# Vectr.net
KiCad netlist of a schematic drawn in EAGLE
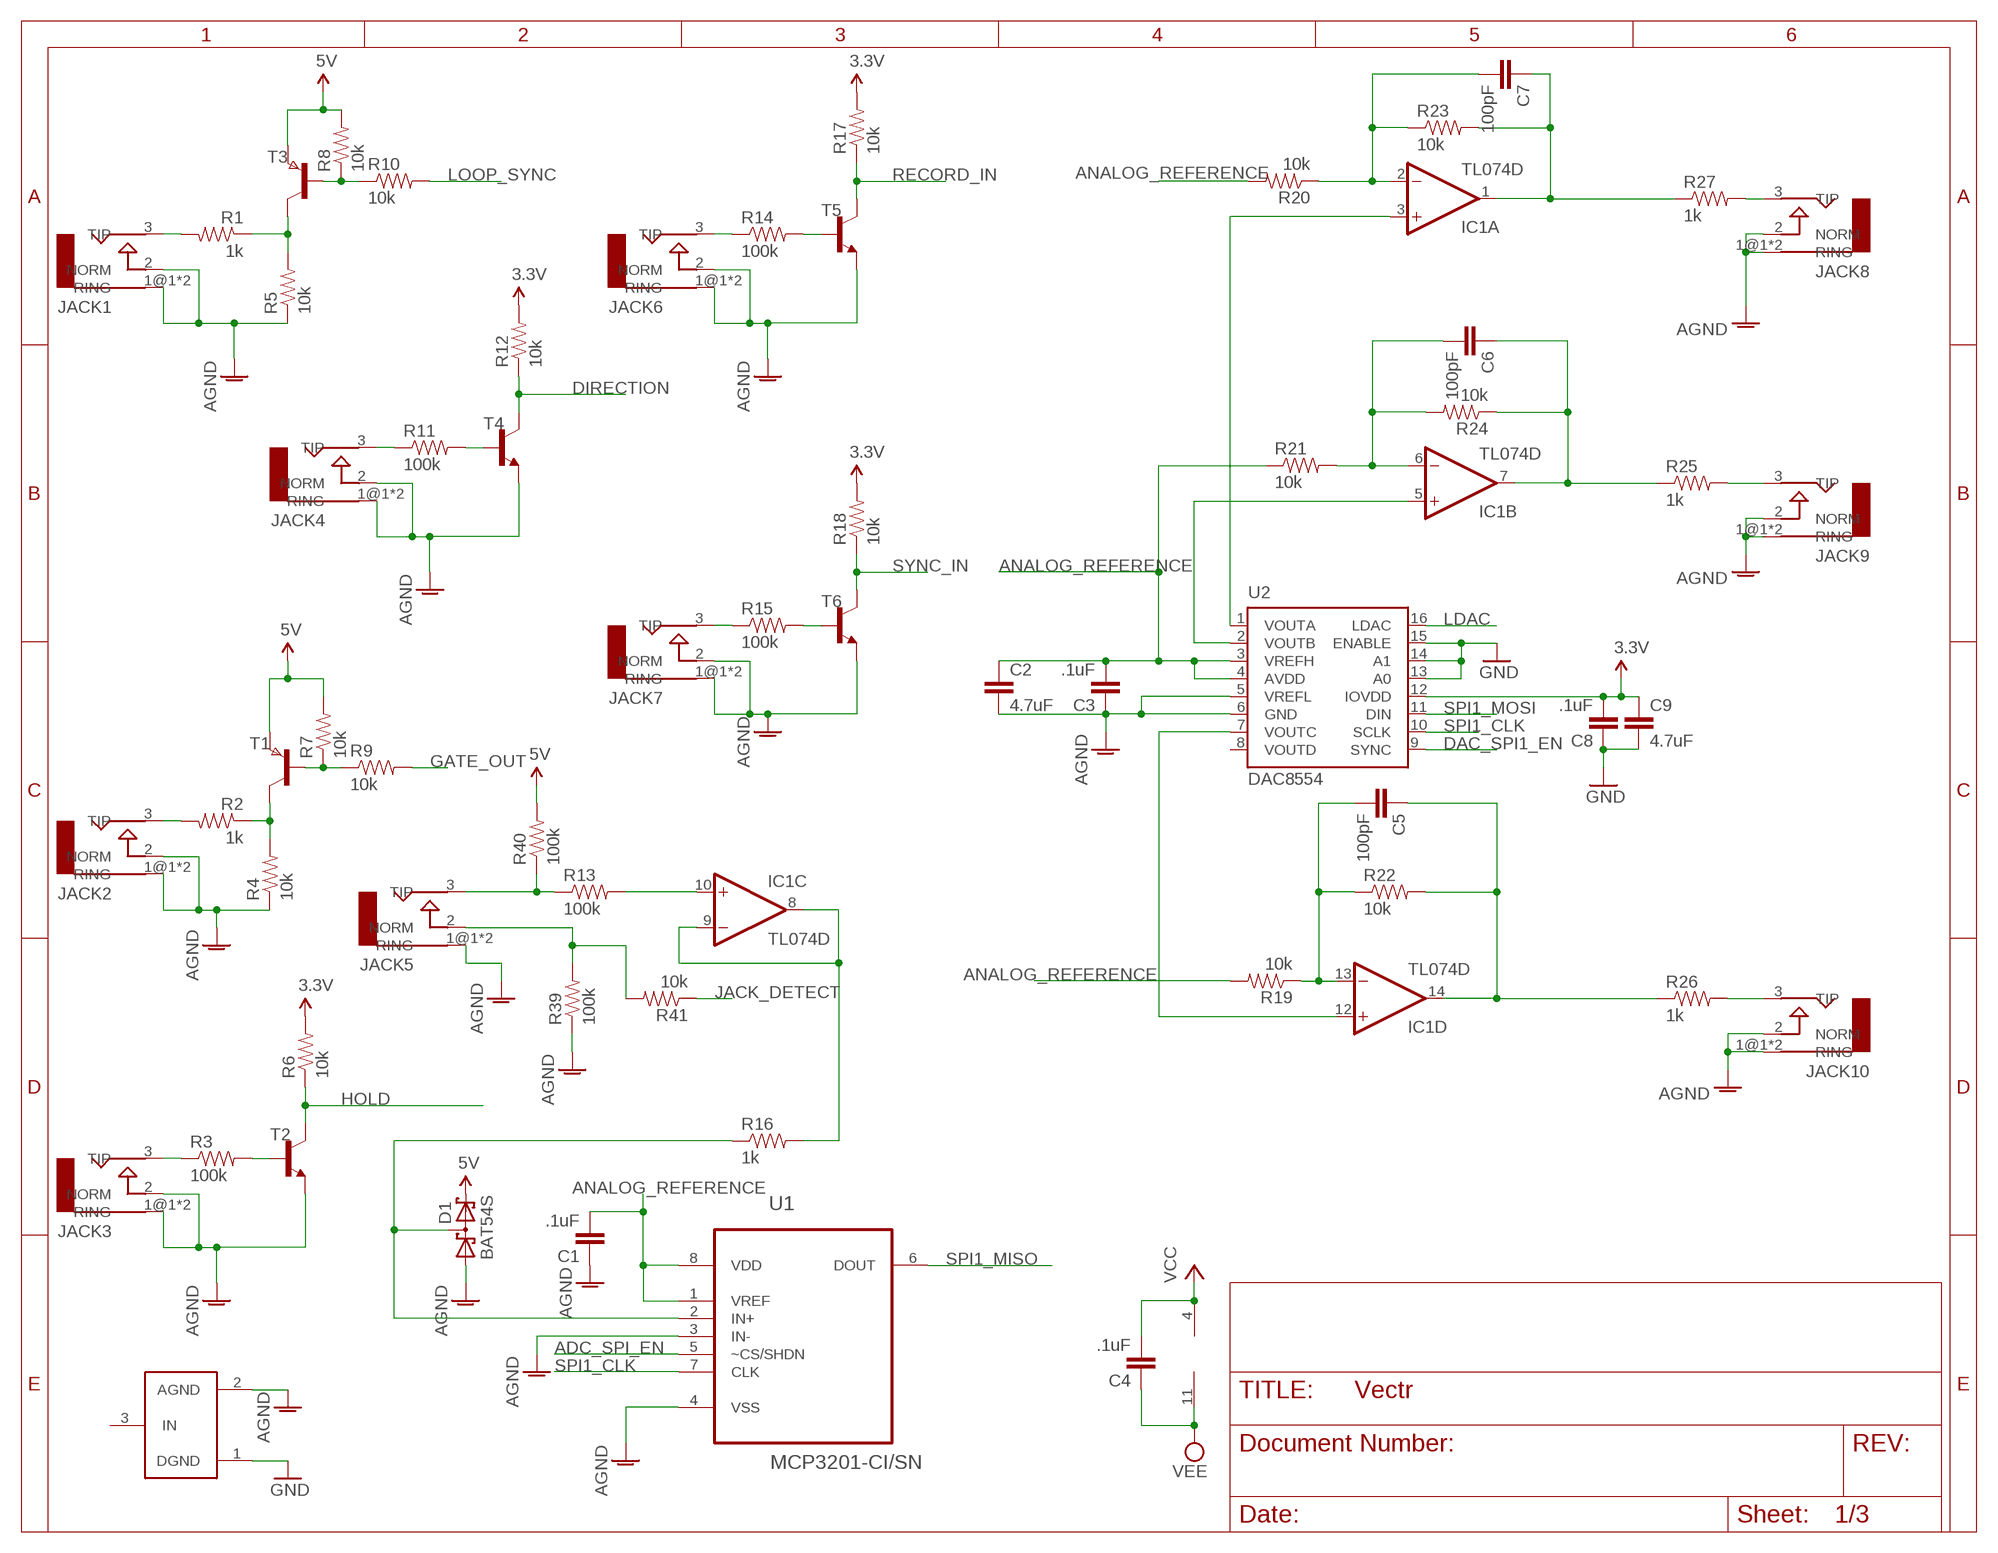
[diagram p0: schematic, sheet 1]
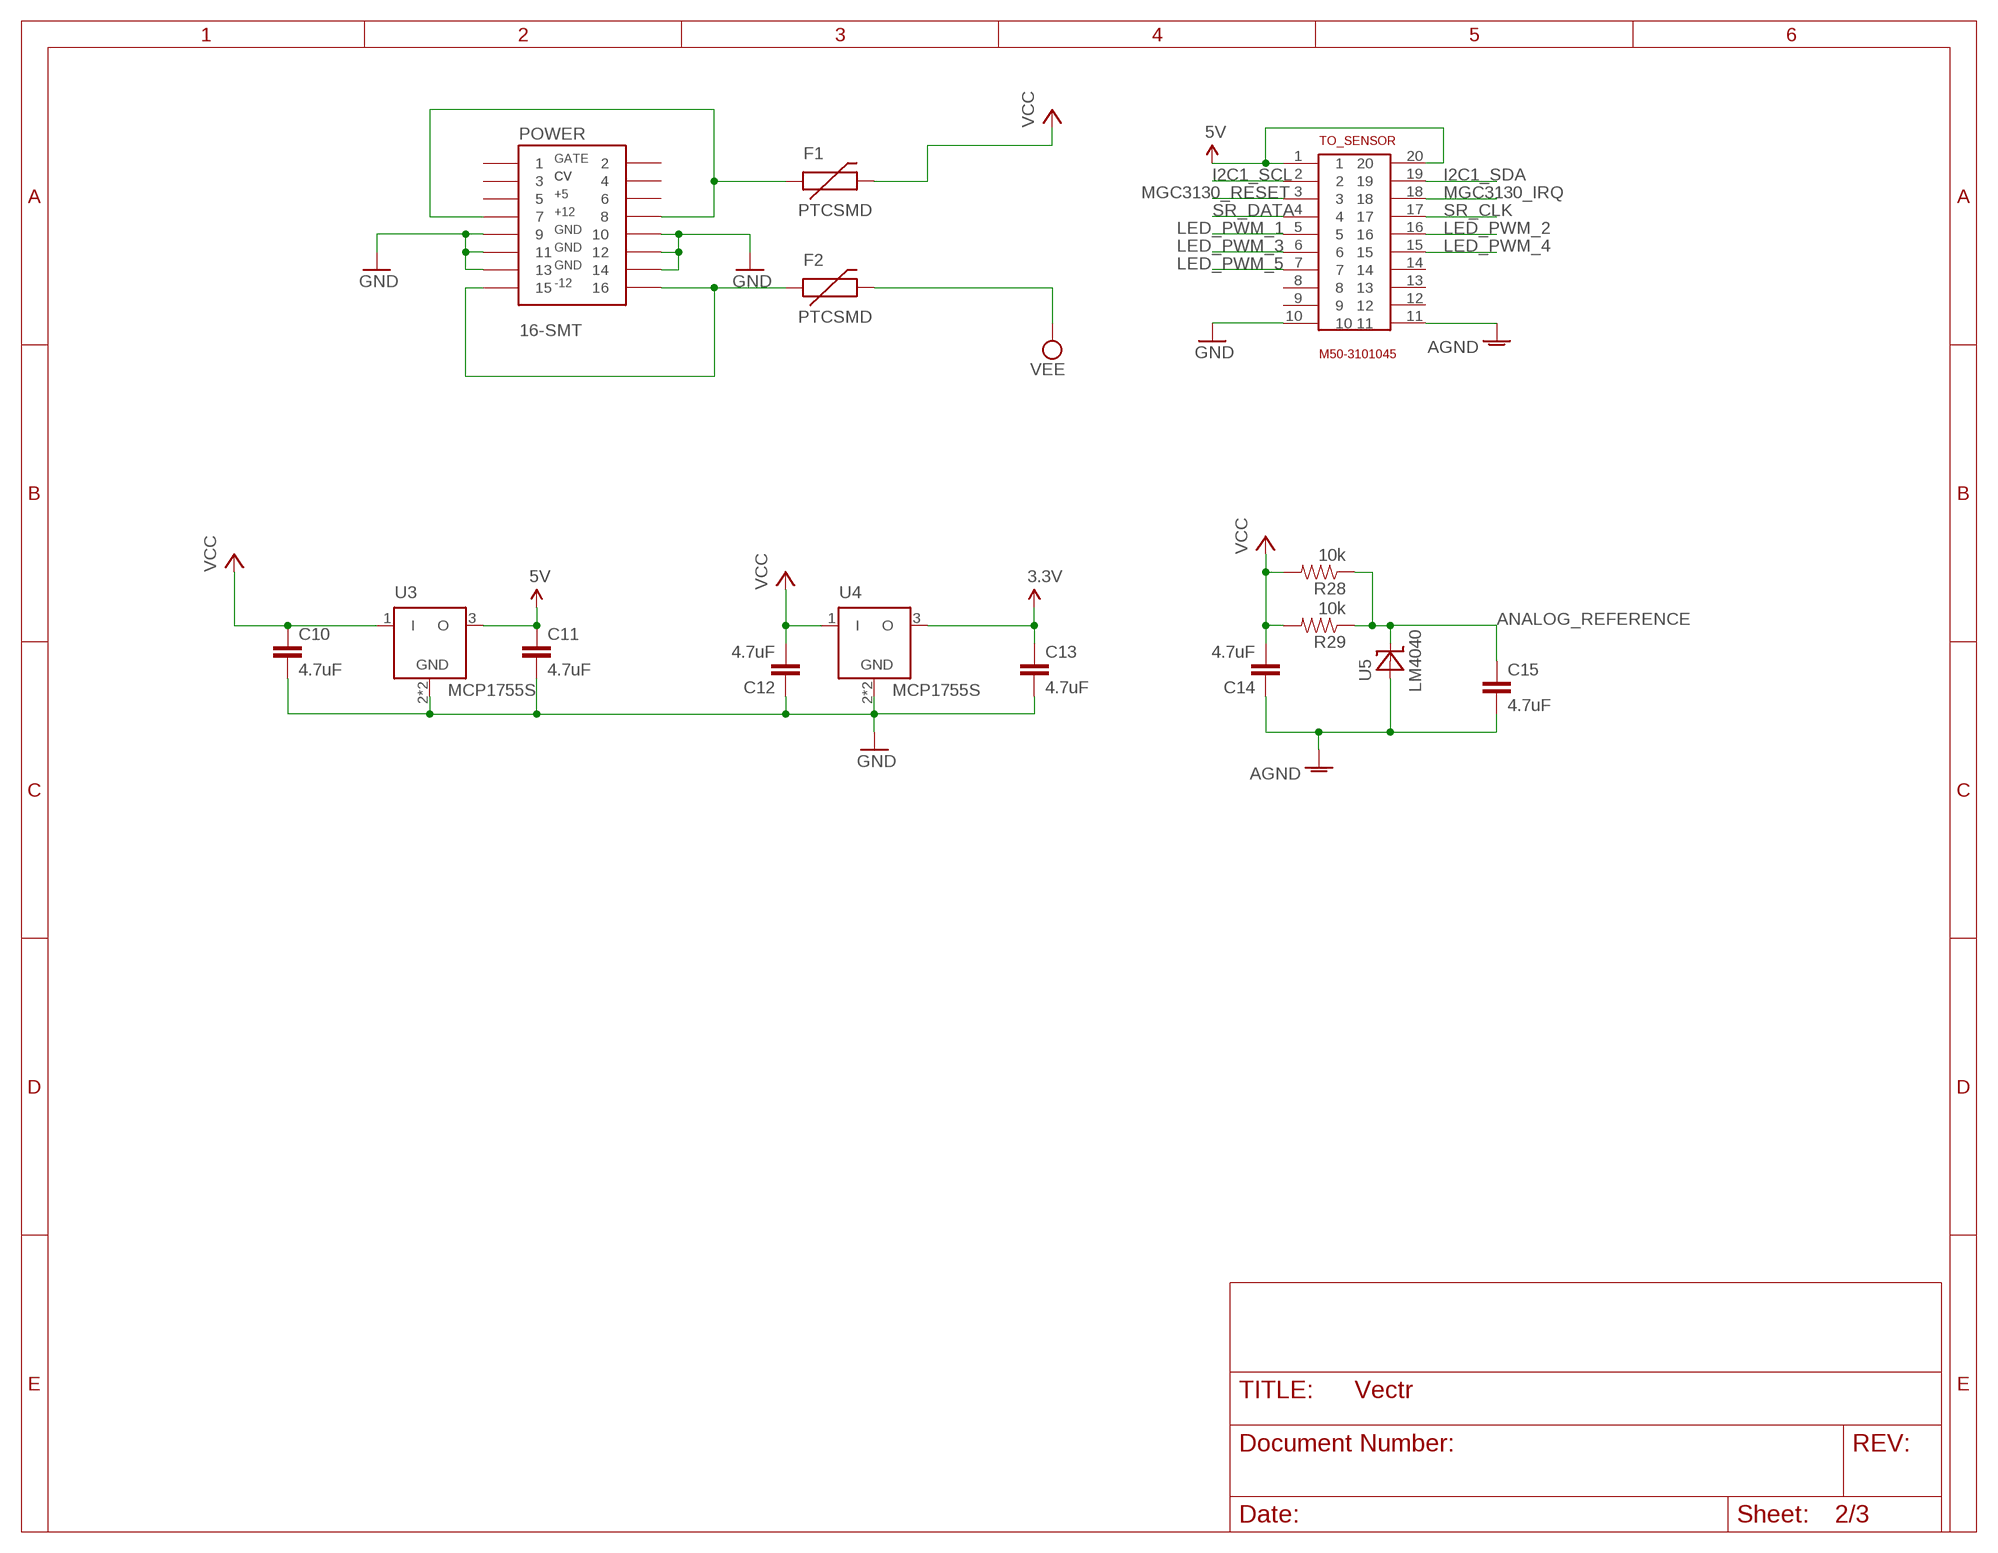
[diagram p1: schematic, sheet 2]
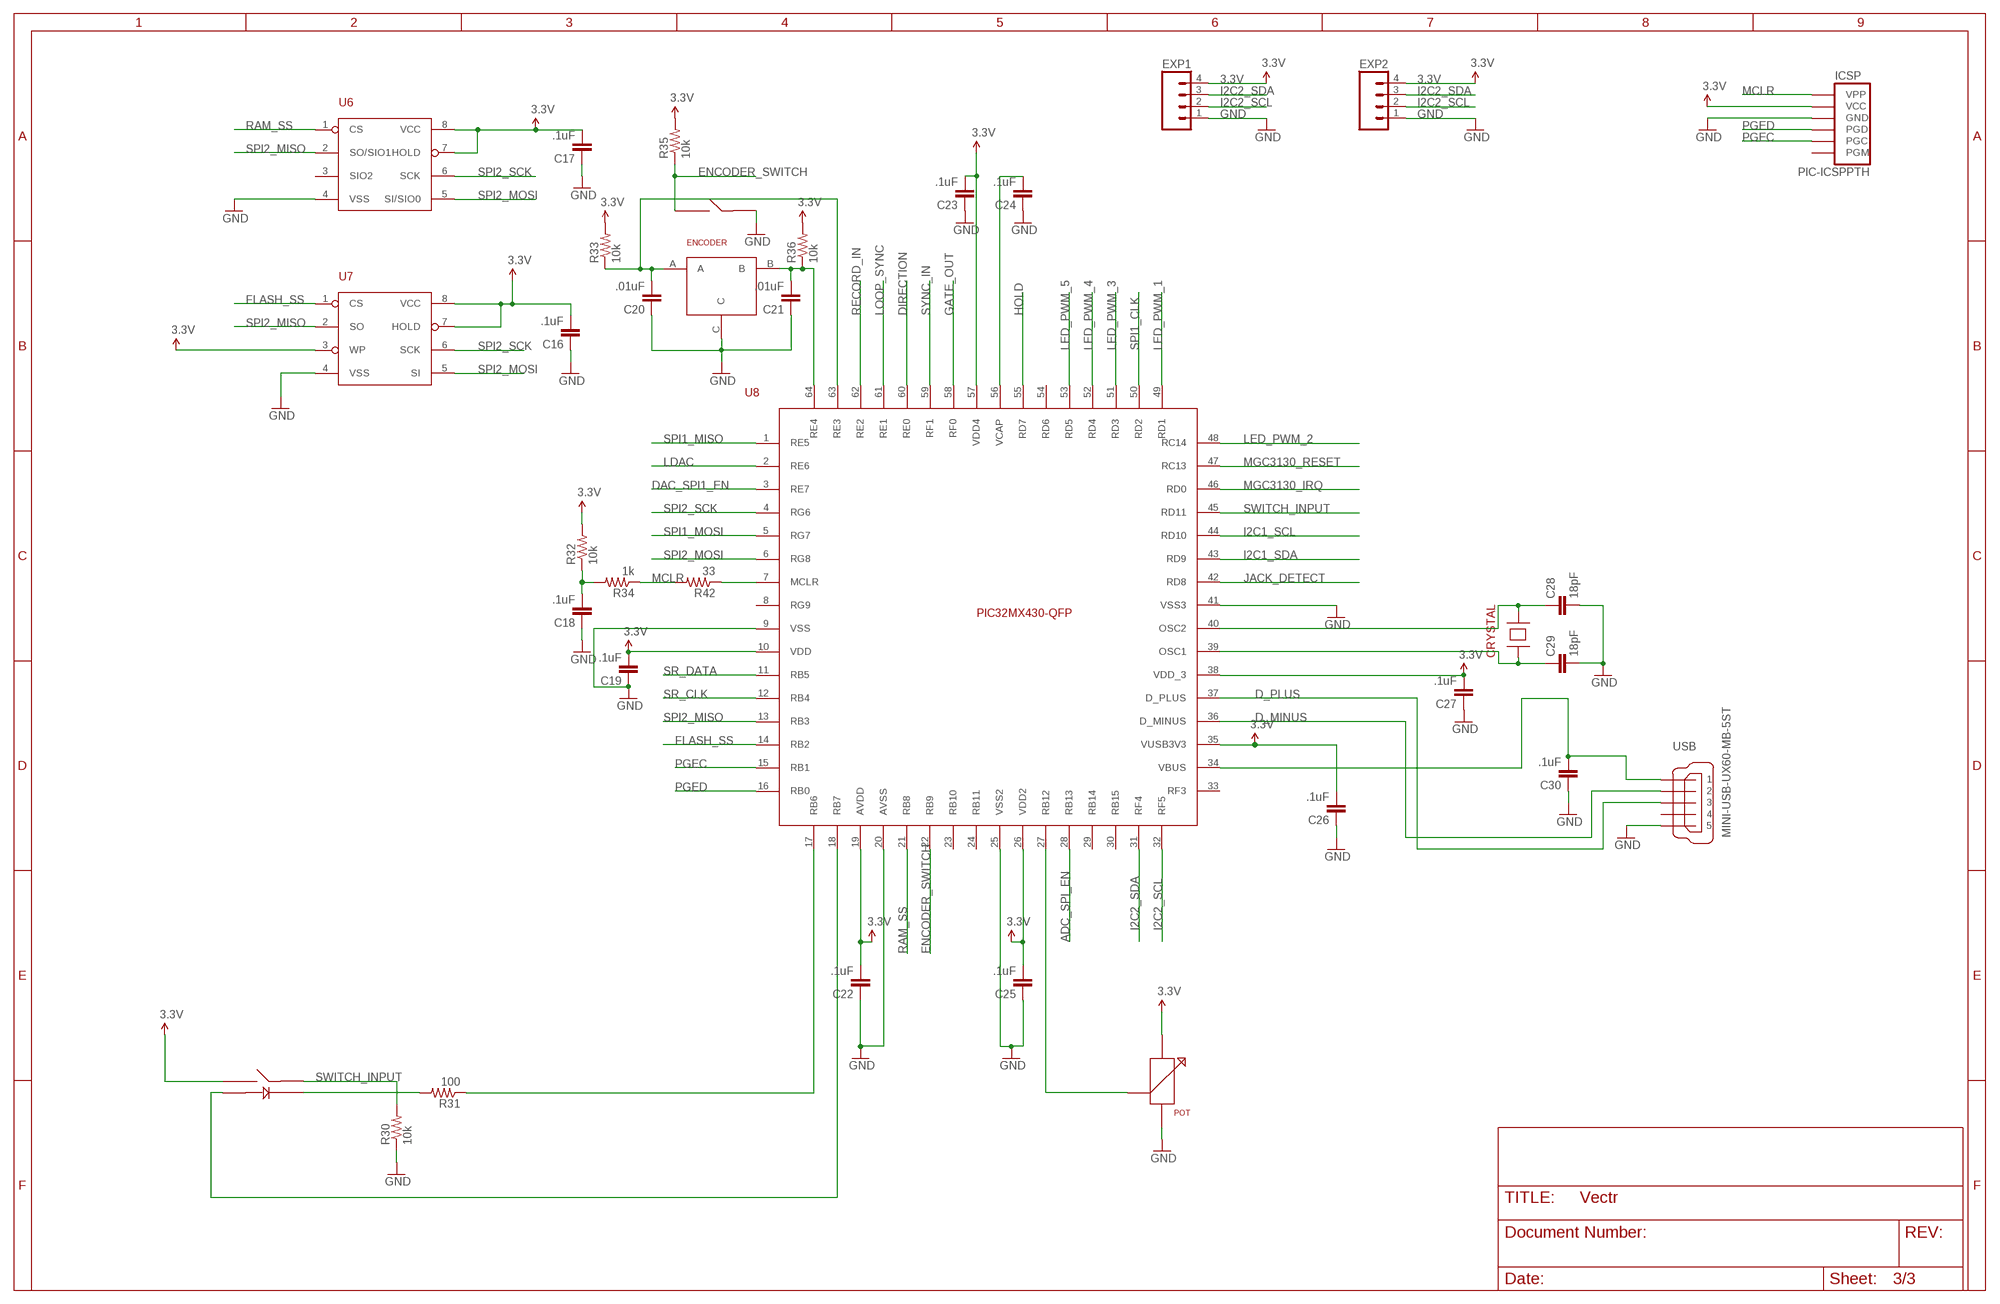
[diagram p2: schematic, sheet 3]

(export (version "E")
  (design (tool "Eeschema 10.0.6"))
  (components
    (comp (ref "C10")
      (value "4.7uF")
      (footprint "eagle-import:0805")
      (libsource (lib "eagle-import") (part "CAP0805"))
    )
    (comp (ref "C11")
      (value "4.7uF")
      (footprint "eagle-import:0805")
      (libsource (lib "eagle-import") (part "CAP0805"))
    )
    (comp (ref "C12")
      (value "4.7uF")
      (footprint "eagle-import:0805")
      (libsource (lib "eagle-import") (part "SparkFun-Passives_CAP0805"))
    )
    (comp (ref "C13")
      (value "4.7uF")
      (footprint "eagle-import:0805")
      (libsource (lib "eagle-import") (part "CAP0805"))
    )
    (comp (ref "C14")
      (value "4.7uF")
      (footprint "eagle-import:0805")
      (libsource (lib "eagle-import") (part "SparkFun-Passives_CAP0805"))
    )
    (comp (ref "C15")
      (value "4.7uF")
      (footprint "eagle-import:0805")
      (libsource (lib "eagle-import") (part "CAP0805"))
    )
    (comp (ref "F1")
      (value "PTCSMD")
      (footprint "eagle-import:PTC-1206")
      (libsource (lib "eagle-import") (part "PTCSMD"))
    )
    (comp (ref "F2")
      (value "PTCSMD")
      (footprint "eagle-import:PTC-1206")
      (libsource (lib "eagle-import") (part "PTCSMD"))
    )
    (comp (ref "POWER")
      (value "16-SMT")
      (footprint "eagle-import:16-SMT")
      (libsource (lib "eagle-import") (part "16-SMT"))
    )
    (comp (ref "R28")
      (value "10k")
      (footprint "eagle-import:0402-RES")
      (libsource (lib "eagle-import") (part "RESISTOR0402-RES"))
    )
    (comp (ref "R29")
      (value "10k")
      (footprint "eagle-import:0402-RES")
      (libsource (lib "eagle-import") (part "RESISTOR0402-RES"))
    )
    (comp (ref "TO_SENSOR")
      (value "M50-3101045")
      (footprint "eagle-import:M50-3101045")
      (libsource (lib "eagle-import") (part "M50-3101045"))
    )
    (comp (ref "U3")
      (value "MCP1755S")
      (footprint "eagle-import:SOT223")
      (libsource (lib "eagle-import") (part "MCP1755S"))
    )
    (comp (ref "U4")
      (value "MCP1755S")
      (footprint "eagle-import:SOT223")
      (libsource (lib "eagle-import") (part "MCP1755S"))
    )
    (comp (ref "U5")
      (value "LM4040")
      (footprint "eagle-import:SOT23")
      (libsource (lib "eagle-import") (part "LM4040"))
    )
    (comp (ref "C1")
      (value ".1uF")
      (footprint "eagle-import:0402-CAP")
      (libsource (lib "eagle-import") (part "SparkFun-Passives_CAP0402-CAP"))
    )
    (comp (ref "C2")
      (value "4.7uF")
      (footprint "eagle-import:0805")
      (libsource (lib "eagle-import") (part "CAP0805"))
    )
    (comp (ref "C3")
      (value ".1uF")
      (footprint "eagle-import:0402-CAP")
      (libsource (lib "eagle-import") (part "SparkFun-Passives_CAP0402-CAP"))
    )
    (comp (ref "C4")
      (value ".1uF")
      (footprint "eagle-import:0402-CAP")
      (libsource (lib "eagle-import") (part "SparkFun-Passives_CAP0402-CAP"))
    )
    (comp (ref "C5")
      (value "100pF")
      (footprint "eagle-import:0402-CAP")
      (libsource (lib "eagle-import") (part "SparkFun-Passives_CAP0402-CAP"))
    )
    (comp (ref "C6")
      (value "100pF")
      (footprint "eagle-import:0402-CAP")
      (libsource (lib "eagle-import") (part "SparkFun-Passives_CAP0402-CAP"))
    )
    (comp (ref "C7")
      (value "100pF")
      (footprint "eagle-import:0402-CAP")
      (libsource (lib "eagle-import") (part "SparkFun-Passives_CAP0402-CAP"))
    )
    (comp (ref "C8")
      (value ".1uF")
      (footprint "eagle-import:0402-CAP")
      (libsource (lib "eagle-import") (part "SparkFun-Passives_CAP0402-CAP"))
    )
    (comp (ref "C9")
      (value "4.7uF")
      (footprint "eagle-import:0805")
      (libsource (lib "eagle-import") (part "CAP0805"))
    )
    (comp (ref "D1")
      (value "BAT54S")
      (footprint "eagle-import:SOT23")
      (libsource (lib "eagle-import") (part "BAT54S"))
    )
    (comp (ref "GND_CONNECT")
      (value "GND_CONNECT")
      (footprint "eagle-import:GND_CONNECT")
      (libsource (lib "eagle-import") (part "GND_CONNECT"))
    )
    (comp (ref "IC1")
      (value "TL074D")
      (footprint "eagle-import:SO14")
      (libsource (lib "eagle-import") (part "TL074D"))
    )
    (comp (ref "JACK1")
      (value "AUDIO-JACKERTHENVAR")
      (footprint "eagle-import:ERTHENVAR-JACK")
      (libsource (lib "eagle-import") (part "AUDIO-JACKERTHENVAR"))
    )
    (comp (ref "JACK2")
      (value "AUDIO-JACKERTHENVAR")
      (footprint "eagle-import:ERTHENVAR-JACK")
      (libsource (lib "eagle-import") (part "AUDIO-JACKERTHENVAR"))
    )
    (comp (ref "JACK3")
      (value "AUDIO-JACKERTHENVAR")
      (footprint "eagle-import:ERTHENVAR-JACK")
      (libsource (lib "eagle-import") (part "AUDIO-JACKERTHENVAR"))
    )
    (comp (ref "JACK4")
      (value "AUDIO-JACKERTHENVAR")
      (footprint "eagle-import:ERTHENVAR-JACK")
      (libsource (lib "eagle-import") (part "AUDIO-JACKERTHENVAR"))
    )
    (comp (ref "JACK5")
      (value "AUDIO-JACKERTHENVAR")
      (footprint "eagle-import:ERTHENVAR-JACK")
      (libsource (lib "eagle-import") (part "AUDIO-JACKERTHENVAR"))
    )
    (comp (ref "JACK6")
      (value "AUDIO-JACKERTHENVAR")
      (footprint "eagle-import:ERTHENVAR-JACK")
      (libsource (lib "eagle-import") (part "AUDIO-JACKERTHENVAR"))
    )
    (comp (ref "JACK7")
      (value "AUDIO-JACKERTHENVAR")
      (footprint "eagle-import:ERTHENVAR-JACK")
      (libsource (lib "eagle-import") (part "AUDIO-JACKERTHENVAR"))
    )
    (comp (ref "JACK8")
      (value "AUDIO-JACKERTHENVAR")
      (footprint "eagle-import:ERTHENVAR-JACK")
      (libsource (lib "eagle-import") (part "AUDIO-JACKERTHENVAR"))
    )
    (comp (ref "JACK9")
      (value "AUDIO-JACKERTHENVAR")
      (footprint "eagle-import:ERTHENVAR-JACK")
      (libsource (lib "eagle-import") (part "AUDIO-JACKERTHENVAR"))
    )
    (comp (ref "JACK10")
      (value "AUDIO-JACKERTHENVAR")
      (footprint "eagle-import:ERTHENVAR-JACK")
      (libsource (lib "eagle-import") (part "AUDIO-JACKERTHENVAR"))
    )
    (comp (ref "R1")
      (value "1k")
      (footprint "eagle-import:0402-RES")
      (libsource (lib "eagle-import") (part "RESISTOR0402-RES"))
    )
    (comp (ref "R2")
      (value "1k")
      (footprint "eagle-import:0402-RES")
      (libsource (lib "eagle-import") (part "RESISTOR0402-RES"))
    )
    (comp (ref "R3")
      (value "100k")
      (footprint "eagle-import:0402-RES")
      (libsource (lib "eagle-import") (part "RESISTOR0402-RES"))
    )
    (comp (ref "R4")
      (value "10k")
      (footprint "eagle-import:0402-RES")
      (libsource (lib "eagle-import") (part "RESISTOR0402-RES"))
    )
    (comp (ref "R5")
      (value "10k")
      (footprint "eagle-import:0402-RES")
      (libsource (lib "eagle-import") (part "RESISTOR0402-RES"))
    )
    (comp (ref "R6")
      (value "10k")
      (footprint "eagle-import:0402-RES")
      (libsource (lib "eagle-import") (part "RESISTOR0402-RES"))
    )
    (comp (ref "R7")
      (value "10k")
      (footprint "eagle-import:0402-RES")
      (libsource (lib "eagle-import") (part "RESISTOR0402-RES"))
    )
    (comp (ref "R8")
      (value "10k")
      (footprint "eagle-import:0402-RES")
      (libsource (lib "eagle-import") (part "RESISTOR0402-RES"))
    )
    (comp (ref "R9")
      (value "10k")
      (footprint "eagle-import:0402-RES")
      (libsource (lib "eagle-import") (part "RESISTOR0402-RES"))
    )
    (comp (ref "R10")
      (value "10k")
      (footprint "eagle-import:0402-RES")
      (libsource (lib "eagle-import") (part "RESISTOR0402-RES"))
    )
    (comp (ref "R11")
      (value "100k")
      (footprint "eagle-import:0402-RES")
      (libsource (lib "eagle-import") (part "RESISTOR0402-RES"))
    )
    (comp (ref "R12")
      (value "10k")
      (footprint "eagle-import:0402-RES")
      (libsource (lib "eagle-import") (part "RESISTOR0402-RES"))
    )
    (comp (ref "R13")
      (value "100k")
      (footprint "eagle-import:0402-RES")
      (libsource (lib "eagle-import") (part "RESISTOR0402-RES"))
    )
    (comp (ref "R14")
      (value "100k")
      (footprint "eagle-import:0402-RES")
      (libsource (lib "eagle-import") (part "RESISTOR0402-RES"))
    )
    (comp (ref "R15")
      (value "100k")
      (footprint "eagle-import:0402-RES")
      (libsource (lib "eagle-import") (part "RESISTOR0402-RES"))
    )
    (comp (ref "R16")
      (value "1k")
      (footprint "eagle-import:0402-RES")
      (libsource (lib "eagle-import") (part "RESISTOR0402-RES"))
    )
    (comp (ref "R17")
      (value "10k")
      (footprint "eagle-import:0402-RES")
      (libsource (lib "eagle-import") (part "RESISTOR0402-RES"))
    )
    (comp (ref "R18")
      (value "10k")
      (footprint "eagle-import:0402-RES")
      (libsource (lib "eagle-import") (part "RESISTOR0402-RES"))
    )
    (comp (ref "R19")
      (value "10k")
      (footprint "eagle-import:0402-RES")
      (libsource (lib "eagle-import") (part "RESISTOR0402-RES"))
    )
    (comp (ref "R20")
      (value "10k")
      (footprint "eagle-import:0402-RES")
      (libsource (lib "eagle-import") (part "RESISTOR0402-RES"))
    )
    (comp (ref "R21")
      (value "10k")
      (footprint "eagle-import:0402-RES")
      (libsource (lib "eagle-import") (part "RESISTOR0402-RES"))
    )
    (comp (ref "R22")
      (value "10k")
      (footprint "eagle-import:0402-RES")
      (libsource (lib "eagle-import") (part "RESISTOR0402-RES"))
    )
    (comp (ref "R23")
      (value "10k")
      (footprint "eagle-import:0402-RES")
      (libsource (lib "eagle-import") (part "RESISTOR0402-RES"))
    )
    (comp (ref "R24")
      (value "10k")
      (footprint "eagle-import:0402-RES")
      (libsource (lib "eagle-import") (part "RESISTOR0402-RES"))
    )
    (comp (ref "R25")
      (value "1k")
      (footprint "eagle-import:0402-RES")
      (libsource (lib "eagle-import") (part "RESISTOR0402-RES"))
    )
    (comp (ref "R26")
      (value "1k")
      (footprint "eagle-import:0402-RES")
      (libsource (lib "eagle-import") (part "RESISTOR0402-RES"))
    )
    (comp (ref "R27")
      (value "1k")
      (footprint "eagle-import:0402-RES")
      (libsource (lib "eagle-import") (part "RESISTOR0402-RES"))
    )
    (comp (ref "R39")
      (value "100k")
      (footprint "eagle-import:0402-RES")
      (libsource (lib "eagle-import") (part "RESISTOR0402-RES"))
    )
    (comp (ref "R40")
      (value "100k")
      (footprint "eagle-import:0402-RES")
      (libsource (lib "eagle-import") (part "RESISTOR0402-RES"))
    )
    (comp (ref "R41")
      (value "10k")
      (footprint "eagle-import:0402-RES")
      (libsource (lib "eagle-import") (part "RESISTOR0402-RES"))
    )
    (comp (ref "T1")
      (value "PNPSOT23")
      (footprint "eagle-import:SOT-23")
      (fields (field (name "MPN") "DSS20200L-7"))
      (libsource (lib "eagle-import") (part "PNPSOT23"))
    )
    (comp (ref "T2")
      (value "TRANSISTOR_NPNSOT23")
      (footprint "eagle-import:SOT23")
      (libsource (lib "eagle-import") (part "TRANSISTOR_NPNSOT23"))
    )
    (comp (ref "T3")
      (value "PNPSOT23")
      (footprint "eagle-import:SOT-23")
      (fields (field (name "MPN") "DSS20200L-7"))
      (libsource (lib "eagle-import") (part "PNPSOT23"))
    )
    (comp (ref "T4")
      (value "TRANSISTOR_NPNSOT23")
      (footprint "eagle-import:SOT23")
      (libsource (lib "eagle-import") (part "TRANSISTOR_NPNSOT23"))
    )
    (comp (ref "T5")
      (value "TRANSISTOR_NPNSOT23")
      (footprint "eagle-import:SOT23")
      (libsource (lib "eagle-import") (part "TRANSISTOR_NPNSOT23"))
    )
    (comp (ref "T6")
      (value "TRANSISTOR_NPNSOT23")
      (footprint "eagle-import:SOT23")
      (libsource (lib "eagle-import") (part "TRANSISTOR_NPNSOT23"))
    )
    (comp (ref "U1")
      (value "MCP3201-CI/SN")
      (footprint "eagle-import:SOIC127P600X175-8N")
      (libsource (lib "eagle-import") (part "MCP3201-CI/SN"))
    )
    (comp (ref "U2")
      (value "DAC8554")
      (footprint "eagle-import:PW_R-PDSO-G16")
      (libsource (lib "eagle-import") (part "DAC8554"))
    )
    (comp (ref "C16")
      (value ".1uF")
      (footprint "eagle-import:0402-CAP")
      (libsource (lib "eagle-import") (part "SparkFun-Passives_CAP0402-CAP"))
    )
    (comp (ref "C17")
      (value ".1uF")
      (footprint "eagle-import:0402-CAP")
      (libsource (lib "eagle-import") (part "SparkFun-Passives_CAP0402-CAP"))
    )
    (comp (ref "C18")
      (value ".1uF")
      (footprint "eagle-import:0402-CAP")
      (libsource (lib "eagle-import") (part "SparkFun-Passives_CAP0402-CAP"))
    )
    (comp (ref "C19")
      (value ".1uF")
      (footprint "eagle-import:0402-CAP")
      (libsource (lib "eagle-import") (part "SparkFun-Passives_CAP0402-CAP"))
    )
    (comp (ref "C20")
      (value ".01uF")
      (footprint "eagle-import:0402-CAP")
      (libsource (lib "eagle-import") (part "SparkFun-Passives_CAP0402-CAP"))
    )
    (comp (ref "C21")
      (value ".01uF")
      (footprint "eagle-import:0402-CAP")
      (libsource (lib "eagle-import") (part "SparkFun-Passives_CAP0402-CAP"))
    )
    (comp (ref "C22")
      (value ".1uF")
      (footprint "eagle-import:0402-CAP")
      (libsource (lib "eagle-import") (part "SparkFun-Passives_CAP0402-CAP"))
    )
    (comp (ref "C23")
      (value ".1uF")
      (footprint "eagle-import:0402-CAP")
      (libsource (lib "eagle-import") (part "SparkFun-Passives_CAP0402-CAP"))
    )
    (comp (ref "C24")
      (value ".1uF")
      (footprint "eagle-import:0402-CAP")
      (libsource (lib "eagle-import") (part "SparkFun-Passives_CAP0402-CAP"))
    )
    (comp (ref "C25")
      (value ".1uF")
      (footprint "eagle-import:0402-CAP")
      (libsource (lib "eagle-import") (part "SparkFun-Passives_CAP0402-CAP"))
    )
    (comp (ref "C26")
      (value ".1uF")
      (footprint "eagle-import:0402-CAP")
      (libsource (lib "eagle-import") (part "SparkFun-Passives_CAP0402-CAP"))
    )
    (comp (ref "C27")
      (value ".1uF")
      (footprint "eagle-import:0402-CAP")
      (libsource (lib "eagle-import") (part "SparkFun-Passives_CAP0402-CAP"))
    )
    (comp (ref "C28")
      (value "18pF")
      (footprint "eagle-import:0402-CAP")
      (libsource (lib "eagle-import") (part "SparkFun-Passives_CAP0402-CAP"))
    )
    (comp (ref "C29")
      (value "18pF")
      (footprint "eagle-import:0402-CAP")
      (libsource (lib "eagle-import") (part "SparkFun-Passives_CAP0402-CAP"))
    )
    (comp (ref "C30")
      (value ".1uF")
      (footprint "eagle-import:0402-CAP")
      (libsource (lib "eagle-import") (part "SparkFun-Passives_CAP0402-CAP"))
    )
    (comp (ref "CRYSTAL")
      (value "SMD-4-CRYSTAL")
      (footprint "eagle-import:SMD-4-CRYSTAL")
      (libsource (lib "eagle-import") (part "SMD-4-CRYSTAL"))
    )
    (comp (ref "ENCODER")
      (value "PEC16_ENCODER")
      (footprint "eagle-import:PEC16_ENCODER")
      (libsource (lib "eagle-import") (part "PEC16_ENCODER"))
    )
    (comp (ref "EXP1")
      (value "M04SMD_STRAIGHT_COMBO")
      (footprint "eagle-import:1X04_SMD_STRAIGHT_COMBO")
      (libsource (lib "eagle-import") (part "M04SMD_STRAIGHT_COMBO"))
    )
    (comp (ref "EXP2")
      (value "M04SMD_STRAIGHT_COMBO")
      (footprint "eagle-import:1X04_SMD_STRAIGHT_COMBO")
      (libsource (lib "eagle-import") (part "M04SMD_STRAIGHT_COMBO"))
    )
    (comp (ref "ICSP")
      (value "PIC-ICSPPTH")
      (footprint "eagle-import:MOLEX-1X6")
      (libsource (lib "eagle-import") (part "PIC-ICSPPTH"))
    )
    (comp (ref "POT")
      (value "9MMPOT")
      (footprint "eagle-import:9MMPOT")
      (libsource (lib "eagle-import") (part "9MMPOT"))
    )
    (comp (ref "R30")
      (value "10k")
      (footprint "eagle-import:0402-RES")
      (libsource (lib "eagle-import") (part "RESISTOR0402-RES"))
    )
    (comp (ref "R31")
      (value "100")
      (footprint "eagle-import:0402-RES")
      (libsource (lib "eagle-import") (part "RESISTOR0402-RES"))
    )
    (comp (ref "R32")
      (value "10k")
      (footprint "eagle-import:0402-RES")
      (libsource (lib "eagle-import") (part "RESISTOR0402-RES"))
    )
    (comp (ref "R33")
      (value "10k")
      (footprint "eagle-import:0402-RES")
      (libsource (lib "eagle-import") (part "RESISTOR0402-RES"))
    )
    (comp (ref "R34")
      (value "1k")
      (footprint "eagle-import:0402-RES")
      (libsource (lib "eagle-import") (part "RESISTOR0402-RES"))
    )
    (comp (ref "R35")
      (value "10k")
      (footprint "eagle-import:0402-RES")
      (libsource (lib "eagle-import") (part "RESISTOR0402-RES"))
    )
    (comp (ref "R36")
      (value "10k")
      (footprint "eagle-import:0402-RES")
      (libsource (lib "eagle-import") (part "RESISTOR0402-RES"))
    )
    (comp (ref "R42")
      (value "33")
      (footprint "eagle-import:0402-RES")
      (libsource (lib "eagle-import") (part "RESISTOR0402-RES"))
    )
    (comp (ref "SWITCH")
      (value "5GSH9")
      (footprint "eagle-import:5GSH9")
      (libsource (lib "eagle-import") (part "5GSH9"))
    )
    (comp (ref "U6")
      (value "23LC512")
      (footprint "eagle-import:SO-08")
      (libsource (lib "eagle-import") (part "23LC512"))
    )
    (comp (ref "U7")
      (value "SST25VF010A")
      (footprint "eagle-import:SO-08")
      (libsource (lib "eagle-import") (part "SST25VF010A"))
    )
    (comp (ref "U8")
      (value "PIC32MX430-QFP")
      (footprint "eagle-import:QFP50P1200X1200X120-64N")
      (libsource (lib "eagle-import") (part "PIC32MX430-QFP"))
    )
    (comp (ref "USB")
      (value "MINI-USB-UX60-MB-5ST")
      (footprint "eagle-import:UX60-MB-5ST")
      (libsource (lib "eagle-import") (part "MINI-USB-UX60-MB-5ST"))
    )
  )
  (nets
    (net (code "1") (name "3.3V") (class "Default")
      (node (ref "C13") (pin "1") (pinfunction "1_1") (pintype "passive"))
      (node (ref "C16") (pin "2") (pinfunction "2_2") (pintype "passive"))
      (node (ref "C17") (pin "2") (pinfunction "2_2") (pintype "passive"))
      (node (ref "C19") (pin "2") (pinfunction "2_2") (pintype "passive"))
      (node (ref "C22") (pin "2") (pinfunction "2_2") (pintype "passive"))
      (node (ref "C23") (pin "2") (pinfunction "2_2") (pintype "passive"))
      (node (ref "C25") (pin "2") (pinfunction "2_2") (pintype "passive"))
      (node (ref "C26") (pin "2") (pinfunction "2_2") (pintype "passive"))
      (node (ref "C27") (pin "2") (pinfunction "2_2") (pintype "passive"))
      (node (ref "C8") (pin "2") (pinfunction "2_2") (pintype "passive"))
      (node (ref "C9") (pin "1") (pinfunction "1_1") (pintype "passive"))
      (node (ref "EXP1") (pin "4") (pinfunction "4_4") (pintype "passive"))
      (node (ref "EXP2") (pin "4") (pinfunction "4_4") (pintype "passive"))
      (node (ref "ICSP") (pin "5") (pinfunction "VCC_5") (pintype "bidirectional"))
      (node (ref "POT") (pin "1") (pinfunction "1_1") (pintype "bidirectional"))
      (node (ref "R12") (pin "2") (pinfunction "2_2") (pintype "passive"))
      (node (ref "R17") (pin "2") (pinfunction "2_2") (pintype "passive"))
      (node (ref "R18") (pin "2") (pinfunction "2_2") (pintype "passive"))
      (node (ref "R32") (pin "2") (pinfunction "2_2") (pintype "passive"))
      (node (ref "R33") (pin "2") (pinfunction "2_2") (pintype "passive"))
      (node (ref "R35") (pin "2") (pinfunction "2_2") (pintype "passive"))
      (node (ref "R36") (pin "2") (pinfunction "2_2") (pintype "passive"))
      (node (ref "R6") (pin "2") (pinfunction "2_2") (pintype "passive"))
      (node (ref "SWITCH") (pin "1") (pinfunction "1_1") (pintype "bidirectional"))
      (node (ref "U2") (pin "12") (pinfunction "IOVDD_12") (pintype "input"))
      (node (ref "U4") (pin "3") (pinfunction "O_3") (pintype "input"))
      (node (ref "U6") (pin "7") (pinfunction "HOLD_7") (pintype "bidirectional"))
      (node (ref "U6") (pin "8") (pinfunction "VCC_8") (pintype "power_in"))
      (node (ref "U7") (pin "3") (pinfunction "WP_3") (pintype "bidirectional"))
      (node (ref "U7") (pin "7") (pinfunction "HOLD_7") (pintype "bidirectional"))
      (node (ref "U7") (pin "8") (pinfunction "VCC_8") (pintype "power_in"))
      (node (ref "U8") (pin "10") (pinfunction "VDD_10") (pintype "bidirectional"))
      (node (ref "U8") (pin "19") (pinfunction "AVDD_19") (pintype "bidirectional"))
      (node (ref "U8") (pin "26") (pinfunction "VDD2_26") (pintype "bidirectional"))
      (node (ref "U8") (pin "35") (pinfunction "VUSB3V3_35") (pintype "bidirectional"))
      (node (ref "U8") (pin "38") (pinfunction "VDD_3_38") (pintype "bidirectional"))
      (node (ref "U8") (pin "57") (pinfunction "VDD4_57") (pintype "bidirectional"))
    )
    (net (code "2") (name "5V") (class "Default")
      (node (ref "C11") (pin "1") (pinfunction "1_1") (pintype "passive"))
      (node (ref "D1") (pin "2") (pinfunction "C2_2") (pintype "passive"))
      (node (ref "R40") (pin "2") (pinfunction "2_2") (pintype "passive"))
      (node (ref "R7") (pin "2") (pinfunction "2_2") (pintype "passive"))
      (node (ref "R8") (pin "2") (pinfunction "2_2") (pintype "passive"))
      (node (ref "T1") (pin "2") (pinfunction "E_2") (pintype "passive"))
      (node (ref "T3") (pin "2") (pinfunction "E_2") (pintype "passive"))
      (node (ref "TO_SENSOR") (pin "1") (pinfunction "1_1") (pintype "bidirectional"))
      (node (ref "TO_SENSOR") (pin "20") (pinfunction "20_20") (pintype "bidirectional"))
      (node (ref "U3") (pin "3") (pinfunction "O_3") (pintype "input"))
    )
    (net (code "3") (name "ADC_SPI_EN") (class "Default")
      (node (ref "U1") (pin "5") (pinfunction "~{CS/SHDN}_5") (pintype "input"))
      (node (ref "U8") (pin "28") (pinfunction "RB13_28") (pintype "bidirectional"))
    )
    (net (code "4") (name "AGND") (class "Default")
      (node (ref "C1") (pin "1") (pinfunction "1_1") (pintype "passive"))
      (node (ref "C14") (pin "1") (pinfunction "1_1") (pintype "passive"))
      (node (ref "C15") (pin "2") (pinfunction "2_2") (pintype "passive"))
      (node (ref "C2") (pin "2") (pinfunction "2_2") (pintype "passive"))
      (node (ref "C3") (pin "1") (pinfunction "1_1") (pintype "passive"))
      (node (ref "D1") (pin "1") (pinfunction "A1_1") (pintype "passive"))
      (node (ref "GND_CONNECT") (pin "2") (pinfunction "AGND_2") (pintype "bidirectional"))
      (node (ref "JACK1") (pin "1@1") (pinfunction "RING_1@1") (pintype "bidirectional"))
      (node (ref "JACK1") (pin "1@2") (pinfunction "RING_1@2") (pintype "bidirectional"))
      (node (ref "JACK1") (pin "2") (pinfunction "NORM_2") (pintype "bidirectional"))
      (node (ref "JACK10") (pin "1@1") (pinfunction "RING_1@1") (pintype "bidirectional"))
      (node (ref "JACK10") (pin "1@2") (pinfunction "RING_1@2") (pintype "bidirectional"))
      (node (ref "JACK10") (pin "2") (pinfunction "NORM_2") (pintype "bidirectional"))
      (node (ref "JACK2") (pin "1@1") (pinfunction "RING_1@1") (pintype "bidirectional"))
      (node (ref "JACK2") (pin "1@2") (pinfunction "RING_1@2") (pintype "bidirectional"))
      (node (ref "JACK2") (pin "2") (pinfunction "NORM_2") (pintype "bidirectional"))
      (node (ref "JACK3") (pin "1@1") (pinfunction "RING_1@1") (pintype "bidirectional"))
      (node (ref "JACK3") (pin "1@2") (pinfunction "RING_1@2") (pintype "bidirectional"))
      (node (ref "JACK3") (pin "2") (pinfunction "NORM_2") (pintype "bidirectional"))
      (node (ref "JACK4") (pin "1@1") (pinfunction "RING_1@1") (pintype "bidirectional"))
      (node (ref "JACK4") (pin "1@2") (pinfunction "RING_1@2") (pintype "bidirectional"))
      (node (ref "JACK4") (pin "2") (pinfunction "NORM_2") (pintype "bidirectional"))
      (node (ref "JACK5") (pin "1@1") (pinfunction "RING_1@1") (pintype "bidirectional"))
      (node (ref "JACK5") (pin "1@2") (pinfunction "RING_1@2") (pintype "bidirectional"))
      (node (ref "JACK6") (pin "1@1") (pinfunction "RING_1@1") (pintype "bidirectional"))
      (node (ref "JACK6") (pin "1@2") (pinfunction "RING_1@2") (pintype "bidirectional"))
      (node (ref "JACK6") (pin "2") (pinfunction "NORM_2") (pintype "bidirectional"))
      (node (ref "JACK7") (pin "1@1") (pinfunction "RING_1@1") (pintype "bidirectional"))
      (node (ref "JACK7") (pin "1@2") (pinfunction "RING_1@2") (pintype "bidirectional"))
      (node (ref "JACK7") (pin "2") (pinfunction "NORM_2") (pintype "bidirectional"))
      (node (ref "JACK8") (pin "1@1") (pinfunction "RING_1@1") (pintype "bidirectional"))
      (node (ref "JACK8") (pin "1@2") (pinfunction "RING_1@2") (pintype "bidirectional"))
      (node (ref "JACK8") (pin "2") (pinfunction "NORM_2") (pintype "bidirectional"))
      (node (ref "JACK9") (pin "1@1") (pinfunction "RING_1@1") (pintype "bidirectional"))
      (node (ref "JACK9") (pin "1@2") (pinfunction "RING_1@2") (pintype "bidirectional"))
      (node (ref "JACK9") (pin "2") (pinfunction "NORM_2") (pintype "bidirectional"))
      (node (ref "R39") (pin "1") (pinfunction "1_1") (pintype "passive"))
      (node (ref "R4") (pin "1") (pinfunction "1_1") (pintype "passive"))
      (node (ref "R5") (pin "1") (pinfunction "1_1") (pintype "passive"))
      (node (ref "T2") (pin "2") (pinfunction "E_2") (pintype "passive"))
      (node (ref "T4") (pin "2") (pinfunction "E_2") (pintype "passive"))
      (node (ref "T5") (pin "2") (pinfunction "E_2") (pintype "passive"))
      (node (ref "T6") (pin "2") (pinfunction "E_2") (pintype "passive"))
      (node (ref "TO_SENSOR") (pin "11") (pinfunction "11_11") (pintype "bidirectional"))
      (node (ref "U1") (pin "3") (pinfunction "IN-_3") (pintype "input"))
      (node (ref "U1") (pin "4") (pinfunction "VSS_4") (pintype "power_in"))
      (node (ref "U2") (pin "5") (pinfunction "VREFL_5") (pintype "input"))
      (node (ref "U2") (pin "6") (pinfunction "GND_6") (pintype "input"))
      (node (ref "U5") (pin "2") (pinfunction "A_2") (pintype "passive"))
    )
    (net (code "5") (name "ANALOG_REFERENCE") (class "Default")
      (node (ref "C1") (pin "2") (pinfunction "2_2") (pintype "passive"))
      (node (ref "C15") (pin "1") (pinfunction "1_1") (pintype "passive"))
      (node (ref "C2") (pin "1") (pinfunction "1_1") (pintype "passive"))
      (node (ref "C3") (pin "2") (pinfunction "2_2") (pintype "passive"))
      (node (ref "R19") (pin "2") (pinfunction "2_2") (pintype "passive"))
      (node (ref "R20") (pin "2") (pinfunction "2_2") (pintype "passive"))
      (node (ref "R21") (pin "1") (pinfunction "1_1") (pintype "passive"))
      (node (ref "R28") (pin "1") (pinfunction "1_1") (pintype "passive"))
      (node (ref "R29") (pin "1") (pinfunction "1_1") (pintype "passive"))
      (node (ref "U1") (pin "1") (pinfunction "VREF_1") (pintype "input"))
      (node (ref "U1") (pin "8") (pinfunction "VDD_8") (pintype "power_in"))
      (node (ref "U2") (pin "3") (pinfunction "VREFH_3") (pintype "input"))
      (node (ref "U2") (pin "4") (pinfunction "AVDD_4") (pintype "input"))
      (node (ref "U5") (pin "3") (pinfunction "C_3") (pintype "passive"))
    )
    (net (code "6") (name "DAC_SPI1_EN") (class "Default")
      (node (ref "U2") (pin "9") (pinfunction "SYNC_9") (pintype "input"))
      (node (ref "U8") (pin "3") (pinfunction "RE7_3") (pintype "bidirectional"))
    )
    (net (code "7") (name "DIRECTION") (class "Default")
      (node (ref "R12") (pin "1") (pinfunction "1_1") (pintype "passive"))
      (node (ref "T4") (pin "3") (pinfunction "C_3") (pintype "passive"))
      (node (ref "U8") (pin "60") (pinfunction "RE0_60") (pintype "bidirectional"))
    )
    (net (code "8") (name "D_MINUS") (class "Default")
      (node (ref "U8") (pin "36") (pinfunction "D_MINUS_36") (pintype "bidirectional"))
      (node (ref "USB") (pin "2") (pinfunction "2_2") (pintype "input"))
    )
    (net (code "9") (name "D_PLUS") (class "Default")
      (node (ref "U8") (pin "37") (pinfunction "D_PLUS_37") (pintype "bidirectional"))
      (node (ref "USB") (pin "3") (pinfunction "3_3") (pintype "input"))
    )
    (net (code "10") (name "ENCODER_SWITCH") (class "Default")
      (node (ref "ENCODER") (pin "D") (pinfunction "D_D") (pintype "bidirectional"))
      (node (ref "R35") (pin "1") (pinfunction "1_1") (pintype "passive"))
      (node (ref "U8") (pin "22") (pinfunction "RB9_22") (pintype "bidirectional"))
    )
    (net (code "11") (name "FLASH_SS") (class "Default")
      (node (ref "U7") (pin "1") (pinfunction "CS_1") (pintype "bidirectional"))
      (node (ref "U8") (pin "14") (pinfunction "RB2_14") (pintype "bidirectional"))
    )
    (net (code "12") (name "GATE_OUT") (class "Default")
      (node (ref "R9") (pin "2") (pinfunction "2_2") (pintype "passive"))
      (node (ref "U8") (pin "58") (pinfunction "RF0_58") (pintype "bidirectional"))
    )
    (net (code "13") (name "GND") (class "Default")
      (node (ref "C10") (pin "2") (pinfunction "2_2") (pintype "passive"))
      (node (ref "C11") (pin "2") (pinfunction "2_2") (pintype "passive"))
      (node (ref "C12") (pin "1") (pinfunction "1_1") (pintype "passive"))
      (node (ref "C13") (pin "2") (pinfunction "2_2") (pintype "passive"))
      (node (ref "C16") (pin "1") (pinfunction "1_1") (pintype "passive"))
      (node (ref "C17") (pin "1") (pinfunction "1_1") (pintype "passive"))
      (node (ref "C18") (pin "1") (pinfunction "1_1") (pintype "passive"))
      (node (ref "C19") (pin "1") (pinfunction "1_1") (pintype "passive"))
      (node (ref "C20") (pin "1") (pinfunction "1_1") (pintype "passive"))
      (node (ref "C21") (pin "1") (pinfunction "1_1") (pintype "passive"))
      (node (ref "C22") (pin "1") (pinfunction "1_1") (pintype "passive"))
      (node (ref "C23") (pin "1") (pinfunction "1_1") (pintype "passive"))
      (node (ref "C24") (pin "1") (pinfunction "1_1") (pintype "passive"))
      (node (ref "C25") (pin "1") (pinfunction "1_1") (pintype "passive"))
      (node (ref "C26") (pin "1") (pinfunction "1_1") (pintype "passive"))
      (node (ref "C27") (pin "1") (pinfunction "1_1") (pintype "passive"))
      (node (ref "C28") (pin "2") (pinfunction "2_2") (pintype "passive"))
      (node (ref "C29") (pin "2") (pinfunction "2_2") (pintype "passive"))
      (node (ref "C30") (pin "1") (pinfunction "1_1") (pintype "passive"))
      (node (ref "C8") (pin "1") (pinfunction "1_1") (pintype "passive"))
      (node (ref "C9") (pin "2") (pinfunction "2_2") (pintype "passive"))
      (node (ref "ENCODER") (pin "C") (pinfunction "C_C") (pintype "bidirectional"))
      (node (ref "ENCODER") (pin "E") (pinfunction "E_E") (pintype "bidirectional"))
      (node (ref "EXP1") (pin "1") (pinfunction "1_1") (pintype "passive"))
      (node (ref "EXP2") (pin "1") (pinfunction "1_1") (pintype "passive"))
      (node (ref "GND_CONNECT") (pin "1") (pinfunction "DGND_1") (pintype "bidirectional"))
      (node (ref "ICSP") (pin "4") (pinfunction "GND_4") (pintype "bidirectional"))
      (node (ref "POT") (pin "3") (pinfunction "3_3") (pintype "bidirectional"))
      (node (ref "POWER") (pin "P$10") (pinfunction "10_P$10") (pintype "bidirectional"))
      (node (ref "POWER") (pin "P$11") (pinfunction "11_P$11") (pintype "bidirectional"))
      (node (ref "POWER") (pin "P$12") (pinfunction "12_P$12") (pintype "bidirectional"))
      (node (ref "POWER") (pin "P$13") (pinfunction "13_P$13") (pintype "bidirectional"))
      (node (ref "POWER") (pin "P$14") (pinfunction "14_P$14") (pintype "bidirectional"))
      (node (ref "POWER") (pin "P$9") (pinfunction "9_P$9") (pintype "bidirectional"))
      (node (ref "R30") (pin "1") (pinfunction "1_1") (pintype "passive"))
      (node (ref "TO_SENSOR") (pin "10") (pinfunction "10_10") (pintype "bidirectional"))
      (node (ref "U2") (pin "13") (pinfunction "A0_13") (pintype "input"))
      (node (ref "U2") (pin "14") (pinfunction "A1_14") (pintype "input"))
      (node (ref "U2") (pin "15") (pinfunction "ENABLE_15") (pintype "input"))
      (node (ref "U3") (pin "2") (pinfunction "GND_2") (pintype "power_in"))
      (node (ref "U3") (pin "4") (pinfunction "GND_4") (pintype "power_in"))
      (node (ref "U4") (pin "2") (pinfunction "GND_2") (pintype "power_in"))
      (node (ref "U4") (pin "4") (pinfunction "GND_4") (pintype "power_in"))
      (node (ref "U6") (pin "4") (pinfunction "VSS_4") (pintype "power_in"))
      (node (ref "U7") (pin "4") (pinfunction "VSS_4") (pintype "power_in"))
      (node (ref "U8") (pin "20") (pinfunction "AVSS_20") (pintype "bidirectional"))
      (node (ref "U8") (pin "25") (pinfunction "VSS2_25") (pintype "bidirectional"))
      (node (ref "U8") (pin "41") (pinfunction "VSS3_41") (pintype "bidirectional"))
      (node (ref "U8") (pin "9") (pinfunction "VSS_9") (pintype "bidirectional"))
      (node (ref "USB") (pin "5") (pinfunction "5_5") (pintype "input"))
    )
    (net (code "14") (name "HOLD") (class "Default")
      (node (ref "R6") (pin "1") (pinfunction "1_1") (pintype "passive"))
      (node (ref "T2") (pin "3") (pinfunction "C_3") (pintype "passive"))
      (node (ref "U8") (pin "55") (pinfunction "RD7_55") (pintype "bidirectional"))
    )
    (net (code "15") (name "I2C1_SCL") (class "Default")
      (node (ref "TO_SENSOR") (pin "2") (pinfunction "2_2") (pintype "bidirectional"))
      (node (ref "U8") (pin "44") (pinfunction "RD10_44") (pintype "bidirectional"))
    )
    (net (code "16") (name "I2C1_SDA") (class "Default")
      (node (ref "TO_SENSOR") (pin "19") (pinfunction "19_19") (pintype "bidirectional"))
      (node (ref "U8") (pin "43") (pinfunction "RD9_43") (pintype "bidirectional"))
    )
    (net (code "17") (name "I2C2_SCL") (class "Default")
      (node (ref "EXP1") (pin "2") (pinfunction "2_2") (pintype "passive"))
      (node (ref "EXP2") (pin "2") (pinfunction "2_2") (pintype "passive"))
      (node (ref "U8") (pin "32") (pinfunction "RF5_32") (pintype "bidirectional"))
    )
    (net (code "18") (name "I2C2_SDA") (class "Default")
      (node (ref "EXP1") (pin "3") (pinfunction "3_3") (pintype "passive"))
      (node (ref "EXP2") (pin "3") (pinfunction "3_3") (pintype "passive"))
      (node (ref "U8") (pin "31") (pinfunction "RF4_31") (pintype "bidirectional"))
    )
    (net (code "19") (name "JACK_DETECT") (class "Default")
      (node (ref "R41") (pin "1") (pinfunction "1_1") (pintype "passive"))
      (node (ref "U8") (pin "42") (pinfunction "RD8_42") (pintype "bidirectional"))
    )
    (net (code "20") (name "LDAC") (class "Default")
      (node (ref "U2") (pin "16") (pinfunction "LDAC_16") (pintype "input"))
      (node (ref "U8") (pin "2") (pinfunction "RE6_2") (pintype "bidirectional"))
    )
    (net (code "21") (name "LED_PWM_1") (class "Default")
      (node (ref "TO_SENSOR") (pin "5") (pinfunction "5_5") (pintype "bidirectional"))
      (node (ref "U8") (pin "49") (pinfunction "RD1_49") (pintype "bidirectional"))
    )
    (net (code "22") (name "LED_PWM_2") (class "Default")
      (node (ref "TO_SENSOR") (pin "16") (pinfunction "16_16") (pintype "bidirectional"))
      (node (ref "U8") (pin "48") (pinfunction "RC14_48") (pintype "bidirectional"))
    )
    (net (code "23") (name "LED_PWM_3") (class "Default")
      (node (ref "TO_SENSOR") (pin "6") (pinfunction "6_6") (pintype "bidirectional"))
      (node (ref "U8") (pin "51") (pinfunction "RD3_51") (pintype "bidirectional"))
    )
    (net (code "24") (name "LED_PWM_4") (class "Default")
      (node (ref "TO_SENSOR") (pin "15") (pinfunction "15_15") (pintype "bidirectional"))
      (node (ref "U8") (pin "52") (pinfunction "RD4_52") (pintype "bidirectional"))
    )
    (net (code "25") (name "LED_PWM_5") (class "Default")
      (node (ref "TO_SENSOR") (pin "7") (pinfunction "7_7") (pintype "bidirectional"))
      (node (ref "U8") (pin "53") (pinfunction "RD5_53") (pintype "bidirectional"))
    )
    (net (code "26") (name "LOOP_SYNC") (class "Default")
      (node (ref "R10") (pin "2") (pinfunction "2_2") (pintype "passive"))
      (node (ref "U8") (pin "61") (pinfunction "RE1_61") (pintype "bidirectional"))
    )
    (net (code "27") (name "MCLR") (class "Default")
      (node (ref "ICSP") (pin "6") (pinfunction "VPP_6") (pintype "bidirectional"))
      (node (ref "R34") (pin "1") (pinfunction "1_1") (pintype "passive"))
      (node (ref "R42") (pin "2") (pinfunction "2_2") (pintype "passive"))
    )
    (net (code "28") (name "MGC3130_IRQ") (class "Default")
      (node (ref "TO_SENSOR") (pin "18") (pinfunction "18_18") (pintype "bidirectional"))
      (node (ref "U8") (pin "46") (pinfunction "RD0_46") (pintype "bidirectional"))
    )
    (net (code "29") (name "MGC3130_RESET") (class "Default")
      (node (ref "TO_SENSOR") (pin "3") (pinfunction "3_3") (pintype "bidirectional"))
      (node (ref "U8") (pin "47") (pinfunction "RC13_47") (pintype "bidirectional"))
    )
    (net (code "30") (name "Net-(C18-Pad2)") (class "Default")
      (node (ref "C18") (pin "2") (pinfunction "2_2") (pintype "passive"))
      (node (ref "R32") (pin "1") (pinfunction "1_1") (pintype "passive"))
      (node (ref "R34") (pin "2") (pinfunction "2_2") (pintype "passive"))
    )
    (net (code "31") (name "Net-(D1-C1A2)") (class "Default")
      (node (ref "D1") (pin "3") (pinfunction "C1A2_3") (pintype "passive"))
      (node (ref "R16") (pin "1") (pinfunction "1_1") (pintype "passive"))
      (node (ref "U1") (pin "2") (pinfunction "IN+_2") (pintype "input"))
    )
    (net (code "32") (name "Net-(IC1A-+IN)") (class "Default")
      (node (ref "IC1") (pin "3") (pinfunction "+IN_3") (pintype "input"))
      (node (ref "U2") (pin "1") (pinfunction "VOUTA_1") (pintype "input"))
    )
    (net (code "33") (name "Net-(IC1A--IN)") (class "Default")
      (node (ref "C7") (pin "2") (pinfunction "2_2") (pintype "passive"))
      (node (ref "IC1") (pin "2") (pinfunction "-IN_2") (pintype "input"))
      (node (ref "R20") (pin "1") (pinfunction "1_1") (pintype "passive"))
      (node (ref "R23") (pin "1") (pinfunction "1_1") (pintype "passive"))
    )
    (net (code "34") (name "Net-(IC1A-OUT)") (class "Default")
      (node (ref "C7") (pin "1") (pinfunction "1_1") (pintype "passive"))
      (node (ref "IC1") (pin "1") (pinfunction "OUT_1") (pintype "output"))
      (node (ref "R23") (pin "2") (pinfunction "2_2") (pintype "passive"))
      (node (ref "R27") (pin "1") (pinfunction "1_1") (pintype "passive"))
    )
    (net (code "35") (name "Net-(IC1B-+IN)") (class "Default")
      (node (ref "IC1") (pin "5") (pinfunction "+IN_5") (pintype "input"))
      (node (ref "U2") (pin "2") (pinfunction "VOUTB_2") (pintype "input"))
    )
    (net (code "36") (name "Net-(IC1B--IN)") (class "Default")
      (node (ref "C6") (pin "2") (pinfunction "2_2") (pintype "passive"))
      (node (ref "IC1") (pin "6") (pinfunction "-IN_6") (pintype "input"))
      (node (ref "R21") (pin "2") (pinfunction "2_2") (pintype "passive"))
      (node (ref "R24") (pin "2") (pinfunction "2_2") (pintype "passive"))
    )
    (net (code "37") (name "Net-(IC1B-OUT)") (class "Default")
      (node (ref "C6") (pin "1") (pinfunction "1_1") (pintype "passive"))
      (node (ref "IC1") (pin "7") (pinfunction "OUT_7") (pintype "output"))
      (node (ref "R24") (pin "1") (pinfunction "1_1") (pintype "passive"))
      (node (ref "R25") (pin "1") (pinfunction "1_1") (pintype "passive"))
    )
    (net (code "38") (name "Net-(IC1C-+IN)") (class "Default")
      (node (ref "IC1") (pin "10") (pinfunction "+IN_10") (pintype "input"))
      (node (ref "R13") (pin "2") (pinfunction "2_2") (pintype "passive"))
    )
    (net (code "39") (name "Net-(IC1C--IN)") (class "Default")
      (node (ref "IC1") (pin "8") (pinfunction "OUT_8") (pintype "output"))
      (node (ref "IC1") (pin "9") (pinfunction "-IN_9") (pintype "input"))
      (node (ref "R16") (pin "2") (pinfunction "2_2") (pintype "passive"))
    )
    (net (code "40") (name "Net-(IC1D-+IN)") (class "Default")
      (node (ref "IC1") (pin "12") (pinfunction "+IN_12") (pintype "input"))
      (node (ref "U2") (pin "7") (pinfunction "VOUTC_7") (pintype "input"))
    )
    (net (code "41") (name "Net-(IC1D--IN)") (class "Default")
      (node (ref "C5") (pin "2") (pinfunction "2_2") (pintype "passive"))
      (node (ref "IC1") (pin "13") (pinfunction "-IN_13") (pintype "input"))
      (node (ref "R19") (pin "1") (pinfunction "1_1") (pintype "passive"))
      (node (ref "R22") (pin "1") (pinfunction "1_1") (pintype "passive"))
    )
    (net (code "42") (name "Net-(IC1D-OUT)") (class "Default")
      (node (ref "C5") (pin "1") (pinfunction "1_1") (pintype "passive"))
      (node (ref "IC1") (pin "14") (pinfunction "OUT_14") (pintype "output"))
      (node (ref "R22") (pin "2") (pinfunction "2_2") (pintype "passive"))
      (node (ref "R26") (pin "1") (pinfunction "1_1") (pintype "passive"))
    )
    (net (code "43") (name "Net-(JACK1-TIP)") (class "Default")
      (node (ref "JACK1") (pin "3") (pinfunction "TIP_3") (pintype "bidirectional"))
      (node (ref "R1") (pin "2") (pinfunction "2_2") (pintype "passive"))
    )
    (net (code "44") (name "Net-(JACK2-TIP)") (class "Default")
      (node (ref "JACK2") (pin "3") (pinfunction "TIP_3") (pintype "bidirectional"))
      (node (ref "R2") (pin "2") (pinfunction "2_2") (pintype "passive"))
    )
    (net (code "45") (name "Net-(JACK3-TIP)") (class "Default")
      (node (ref "JACK3") (pin "3") (pinfunction "TIP_3") (pintype "bidirectional"))
      (node (ref "R3") (pin "1") (pinfunction "1_1") (pintype "passive"))
    )
    (net (code "46") (name "Net-(JACK4-TIP)") (class "Default")
      (node (ref "JACK4") (pin "3") (pinfunction "TIP_3") (pintype "bidirectional"))
      (node (ref "R11") (pin "1") (pinfunction "1_1") (pintype "passive"))
    )
    (net (code "47") (name "Net-(JACK5-NORM)") (class "Default")
      (node (ref "JACK5") (pin "2") (pinfunction "NORM_2") (pintype "bidirectional"))
      (node (ref "R39") (pin "2") (pinfunction "2_2") (pintype "passive"))
      (node (ref "R41") (pin "2") (pinfunction "2_2") (pintype "passive"))
    )
    (net (code "48") (name "Net-(JACK5-TIP)") (class "Default")
      (node (ref "JACK5") (pin "3") (pinfunction "TIP_3") (pintype "bidirectional"))
      (node (ref "R13") (pin "1") (pinfunction "1_1") (pintype "passive"))
      (node (ref "R40") (pin "1") (pinfunction "1_1") (pintype "passive"))
    )
    (net (code "49") (name "Net-(JACK6-TIP)") (class "Default")
      (node (ref "JACK6") (pin "3") (pinfunction "TIP_3") (pintype "bidirectional"))
      (node (ref "R14") (pin "1") (pinfunction "1_1") (pintype "passive"))
    )
    (net (code "50") (name "Net-(JACK7-TIP)") (class "Default")
      (node (ref "JACK7") (pin "3") (pinfunction "TIP_3") (pintype "bidirectional"))
      (node (ref "R15") (pin "1") (pinfunction "1_1") (pintype "passive"))
    )
    (net (code "51") (name "Net-(JACK8-TIP)") (class "Default")
      (node (ref "JACK8") (pin "3") (pinfunction "TIP_3") (pintype "bidirectional"))
      (node (ref "R27") (pin "2") (pinfunction "2_2") (pintype "passive"))
    )
    (net (code "52") (name "Net-(JACK9-TIP)") (class "Default")
      (node (ref "JACK9") (pin "3") (pinfunction "TIP_3") (pintype "bidirectional"))
      (node (ref "R25") (pin "2") (pinfunction "2_2") (pintype "passive"))
    )
    (net (code "53") (name "Net-(JACK10-TIP)") (class "Default")
      (node (ref "JACK10") (pin "3") (pinfunction "TIP_3") (pintype "bidirectional"))
      (node (ref "R26") (pin "2") (pinfunction "2_2") (pintype "passive"))
    )
    (net (code "54") (name "Net-(POWER-7)") (class "Default")
      (node (ref "F1") (pin "1") (pinfunction "1_1") (pintype "bidirectional"))
      (node (ref "POWER") (pin "P$7") (pinfunction "7_P$7") (pintype "bidirectional"))
      (node (ref "POWER") (pin "P$8") (pinfunction "8_P$8") (pintype "bidirectional"))
    )
    (net (code "55") (name "Net-(POWER-15)") (class "Default")
      (node (ref "F2") (pin "1") (pinfunction "1_1") (pintype "bidirectional"))
      (node (ref "POWER") (pin "P$15") (pinfunction "15_P$15") (pintype "bidirectional"))
      (node (ref "POWER") (pin "P$16") (pinfunction "16_P$16") (pintype "bidirectional"))
    )
    (net (code "56") (name "Net-(R31-Pad2)") (class "Default")
      (node (ref "R31") (pin "2") (pinfunction "2_2") (pintype "passive"))
      (node (ref "SWITCH") (pin "2") (pinfunction "2_2") (pintype "bidirectional"))
    )
    (net (code "57") (name "Net-(T1-B)") (class "Default")
      (node (ref "R7") (pin "1") (pinfunction "1_1") (pintype "passive"))
      (node (ref "R9") (pin "1") (pinfunction "1_1") (pintype "passive"))
      (node (ref "T1") (pin "3") (pinfunction "B_3") (pintype "passive"))
    )
    (net (code "58") (name "Net-(T1-C)") (class "Default")
      (node (ref "R2") (pin "1") (pinfunction "1_1") (pintype "passive"))
      (node (ref "R4") (pin "2") (pinfunction "2_2") (pintype "passive"))
      (node (ref "T1") (pin "1") (pinfunction "C_1") (pintype "passive"))
    )
    (net (code "59") (name "Net-(T2-B)") (class "Default")
      (node (ref "R3") (pin "2") (pinfunction "2_2") (pintype "passive"))
      (node (ref "T2") (pin "1") (pinfunction "B_1") (pintype "passive"))
    )
    (net (code "60") (name "Net-(T3-B)") (class "Default")
      (node (ref "R10") (pin "1") (pinfunction "1_1") (pintype "passive"))
      (node (ref "R8") (pin "1") (pinfunction "1_1") (pintype "passive"))
      (node (ref "T3") (pin "3") (pinfunction "B_3") (pintype "passive"))
    )
    (net (code "61") (name "Net-(T3-C)") (class "Default")
      (node (ref "R1") (pin "1") (pinfunction "1_1") (pintype "passive"))
      (node (ref "R5") (pin "2") (pinfunction "2_2") (pintype "passive"))
      (node (ref "T3") (pin "1") (pinfunction "C_1") (pintype "passive"))
    )
    (net (code "62") (name "Net-(T4-B)") (class "Default")
      (node (ref "R11") (pin "2") (pinfunction "2_2") (pintype "passive"))
      (node (ref "T4") (pin "1") (pinfunction "B_1") (pintype "passive"))
    )
    (net (code "63") (name "Net-(T5-B)") (class "Default")
      (node (ref "R14") (pin "2") (pinfunction "2_2") (pintype "passive"))
      (node (ref "T5") (pin "1") (pinfunction "B_1") (pintype "passive"))
    )
    (net (code "64") (name "Net-(T6-B)") (class "Default")
      (node (ref "R15") (pin "2") (pinfunction "2_2") (pintype "passive"))
      (node (ref "T6") (pin "1") (pinfunction "B_1") (pintype "passive"))
    )
    (net (code "65") (name "Net-(U8-MCLR)") (class "Default")
      (node (ref "R42") (pin "1") (pinfunction "1_1") (pintype "passive"))
      (node (ref "U8") (pin "7") (pinfunction "MCLR_7") (pintype "bidirectional"))
    )
    (net (code "66") (name "Net-(U8-OSC1)") (class "Default")
      (node (ref "C29") (pin "1") (pinfunction "1_1") (pintype "passive"))
      (node (ref "CRYSTAL") (pin "1") (pinfunction "1_1") (pintype "bidirectional"))
      (node (ref "U8") (pin "39") (pinfunction "OSC1_39") (pintype "bidirectional"))
    )
    (net (code "67") (name "Net-(U8-OSC2)") (class "Default")
      (node (ref "C28") (pin "1") (pinfunction "1_1") (pintype "passive"))
      (node (ref "CRYSTAL") (pin "3") (pinfunction "3_3") (pintype "bidirectional"))
      (node (ref "U8") (pin "40") (pinfunction "OSC2_40") (pintype "bidirectional"))
    )
    (net (code "68") (name "Net-(U8-RB6)") (class "Default")
      (node (ref "R31") (pin "1") (pinfunction "1_1") (pintype "passive"))
      (node (ref "U8") (pin "17") (pinfunction "RB6_17") (pintype "bidirectional"))
    )
    (net (code "69") (name "Net-(U8-RB7)") (class "Default")
      (node (ref "SWITCH") (pin "3") (pinfunction "3_3") (pintype "bidirectional"))
      (node (ref "U8") (pin "18") (pinfunction "RB7_18") (pintype "bidirectional"))
    )
    (net (code "70") (name "Net-(U8-RB12)") (class "Default")
      (node (ref "POT") (pin "2") (pinfunction "2_2") (pintype "bidirectional"))
      (node (ref "U8") (pin "27") (pinfunction "RB12_27") (pintype "bidirectional"))
    )
    (net (code "71") (name "Net-(U8-RE3)") (class "Default")
      (node (ref "C20") (pin "2") (pinfunction "2_2") (pintype "passive"))
      (node (ref "ENCODER") (pin "A") (pinfunction "A_A") (pintype "bidirectional"))
      (node (ref "R33") (pin "1") (pinfunction "1_1") (pintype "passive"))
      (node (ref "U8") (pin "63") (pinfunction "RE3_63") (pintype "bidirectional"))
    )
    (net (code "72") (name "Net-(U8-RE4)") (class "Default")
      (node (ref "C21") (pin "2") (pinfunction "2_2") (pintype "passive"))
      (node (ref "ENCODER") (pin "B") (pinfunction "B_B") (pintype "bidirectional"))
      (node (ref "R36") (pin "1") (pinfunction "1_1") (pintype "passive"))
      (node (ref "U8") (pin "64") (pinfunction "RE4_64") (pintype "bidirectional"))
    )
    (net (code "73") (name "Net-(U8-VBUS)") (class "Default")
      (node (ref "C30") (pin "2") (pinfunction "2_2") (pintype "passive"))
      (node (ref "U8") (pin "34") (pinfunction "VBUS_34") (pintype "bidirectional"))
      (node (ref "USB") (pin "1") (pinfunction "1_1") (pintype "input"))
    )
    (net (code "74") (name "Net-(U8-VCAP)") (class "Default")
      (node (ref "C24") (pin "2") (pinfunction "2_2") (pintype "passive"))
      (node (ref "U8") (pin "56") (pinfunction "VCAP_56") (pintype "bidirectional"))
    )
    (net (code "75") (name "PGEC") (class "Default")
      (node (ref "ICSP") (pin "2") (pinfunction "PGC_2") (pintype "bidirectional"))
      (node (ref "U8") (pin "15") (pinfunction "RB1_15") (pintype "bidirectional"))
    )
    (net (code "76") (name "PGED") (class "Default")
      (node (ref "ICSP") (pin "3") (pinfunction "PGD_3") (pintype "bidirectional"))
      (node (ref "U8") (pin "16") (pinfunction "RB0_16") (pintype "bidirectional"))
    )
    (net (code "77") (name "RAM_SS") (class "Default")
      (node (ref "U6") (pin "1") (pinfunction "CS_1") (pintype "bidirectional"))
      (node (ref "U8") (pin "21") (pinfunction "RB8_21") (pintype "bidirectional"))
    )
    (net (code "78") (name "RECORD_IN") (class "Default")
      (node (ref "R17") (pin "1") (pinfunction "1_1") (pintype "passive"))
      (node (ref "T5") (pin "3") (pinfunction "C_3") (pintype "passive"))
      (node (ref "U8") (pin "62") (pinfunction "RE2_62") (pintype "bidirectional"))
    )
    (net (code "79") (name "SPI1_CLK") (class "Default")
      (node (ref "U1") (pin "7") (pinfunction "CLK_7") (pintype "input"))
      (node (ref "U2") (pin "10") (pinfunction "SCLK_10") (pintype "input"))
      (node (ref "U8") (pin "50") (pinfunction "RD2_50") (pintype "bidirectional"))
    )
    (net (code "80") (name "SPI1_MISO") (class "Default")
      (node (ref "U1") (pin "6") (pinfunction "DOUT_6") (pintype "output"))
      (node (ref "U8") (pin "1") (pinfunction "RE5_1") (pintype "bidirectional"))
    )
    (net (code "81") (name "SPI1_MOSI") (class "Default")
      (node (ref "U2") (pin "11") (pinfunction "DIN_11") (pintype "input"))
      (node (ref "U8") (pin "5") (pinfunction "RG7_5") (pintype "bidirectional"))
    )
    (net (code "82") (name "SPI2_MISO") (class "Default")
      (node (ref "U6") (pin "2") (pinfunction "SO/SIO1_2") (pintype "bidirectional"))
      (node (ref "U7") (pin "2") (pinfunction "SO_2") (pintype "bidirectional"))
      (node (ref "U8") (pin "13") (pinfunction "RB3_13") (pintype "bidirectional"))
    )
    (net (code "83") (name "SPI2_MOSI") (class "Default")
      (node (ref "U6") (pin "5") (pinfunction "SI/SIO0_5") (pintype "bidirectional"))
      (node (ref "U7") (pin "5") (pinfunction "SI_5") (pintype "bidirectional"))
      (node (ref "U8") (pin "6") (pinfunction "RG8_6") (pintype "bidirectional"))
    )
    (net (code "84") (name "SPI2_SCK") (class "Default")
      (node (ref "U6") (pin "6") (pinfunction "SCK_6") (pintype "bidirectional"))
      (node (ref "U7") (pin "6") (pinfunction "SCK_6") (pintype "bidirectional"))
      (node (ref "U8") (pin "4") (pinfunction "RG6_4") (pintype "bidirectional"))
    )
    (net (code "85") (name "SR_CLK") (class "Default")
      (node (ref "TO_SENSOR") (pin "17") (pinfunction "17_17") (pintype "bidirectional"))
      (node (ref "U8") (pin "12") (pinfunction "RB4_12") (pintype "bidirectional"))
    )
    (net (code "86") (name "SR_DATA") (class "Default")
      (node (ref "TO_SENSOR") (pin "4") (pinfunction "4_4") (pintype "bidirectional"))
      (node (ref "U8") (pin "11") (pinfunction "RB5_11") (pintype "bidirectional"))
    )
    (net (code "87") (name "SWITCH_INPUT") (class "Default")
      (node (ref "R30") (pin "2") (pinfunction "2_2") (pintype "passive"))
      (node (ref "SWITCH") (pin "4") (pinfunction "4_4") (pintype "bidirectional"))
      (node (ref "U8") (pin "45") (pinfunction "RD11_45") (pintype "bidirectional"))
    )
    (net (code "88") (name "SYNC_IN") (class "Default")
      (node (ref "R18") (pin "1") (pinfunction "1_1") (pintype "passive"))
      (node (ref "T6") (pin "3") (pinfunction "C_3") (pintype "passive"))
      (node (ref "U8") (pin "59") (pinfunction "RF1_59") (pintype "bidirectional"))
    )
    (net (code "89") (name "VCC") (class "Default")
      (node (ref "C10") (pin "1") (pinfunction "1_1") (pintype "passive"))
      (node (ref "C12") (pin "2") (pinfunction "2_2") (pintype "passive"))
      (node (ref "C14") (pin "2") (pinfunction "2_2") (pintype "passive"))
      (node (ref "C4") (pin "2") (pinfunction "2_2") (pintype "passive"))
      (node (ref "F1") (pin "2") (pinfunction "2_2") (pintype "bidirectional"))
      (node (ref "IC1") (pin "4") (pinfunction "V+_4") (pintype "power_in"))
      (node (ref "R28") (pin "2") (pinfunction "2_2") (pintype "passive"))
      (node (ref "R29") (pin "2") (pinfunction "2_2") (pintype "passive"))
      (node (ref "U3") (pin "1") (pinfunction "I_1") (pintype "input"))
      (node (ref "U4") (pin "1") (pinfunction "I_1") (pintype "input"))
    )
    (net (code "90") (name "VEE") (class "Default")
      (node (ref "C4") (pin "1") (pinfunction "1_1") (pintype "passive"))
      (node (ref "F2") (pin "2") (pinfunction "2_2") (pintype "bidirectional"))
      (node (ref "IC1") (pin "11") (pinfunction "V-_11") (pintype "power_in"))
    )
    (net (code "91") (name "unconnected-(GND_CONNECT-IN-Pad3)") (class "Default")
      (node (ref "GND_CONNECT") (pin "3") (pinfunction "IN_3") (pintype "bidirectional"))
    )
    (net (code "92") (name "unconnected-(ICSP-PGM-Pad1)") (class "Default")
      (node (ref "ICSP") (pin "1") (pinfunction "PGM_1") (pintype "bidirectional"))
    )
    (net (code "93") (name "unconnected-(POWER-1-PadP$1)") (class "Default")
      (node (ref "POWER") (pin "P$1") (pinfunction "1_P$1") (pintype "bidirectional"))
    )
    (net (code "94") (name "unconnected-(POWER-2-PadP$2)") (class "Default")
      (node (ref "POWER") (pin "P$2") (pinfunction "2_P$2") (pintype "bidirectional"))
    )
    (net (code "95") (name "unconnected-(POWER-3-PadP$3)") (class "Default")
      (node (ref "POWER") (pin "P$3") (pinfunction "3_P$3") (pintype "bidirectional"))
    )
    (net (code "96") (name "unconnected-(POWER-4-PadP$4)") (class "Default")
      (node (ref "POWER") (pin "P$4") (pinfunction "4_P$4") (pintype "bidirectional"))
    )
    (net (code "97") (name "unconnected-(POWER-5-PadP$5)") (class "Default")
      (node (ref "POWER") (pin "P$5") (pinfunction "5_P$5") (pintype "bidirectional"))
    )
    (net (code "98") (name "unconnected-(POWER-6-PadP$6)") (class "Default")
      (node (ref "POWER") (pin "P$6") (pinfunction "6_P$6") (pintype "bidirectional"))
    )
    (net (code "99") (name "unconnected-(TO_SENSOR-Pad8)") (class "Default")
      (node (ref "TO_SENSOR") (pin "8") (pinfunction "8_8") (pintype "bidirectional"))
    )
    (net (code "100") (name "unconnected-(TO_SENSOR-Pad9)") (class "Default")
      (node (ref "TO_SENSOR") (pin "9") (pinfunction "9_9") (pintype "bidirectional"))
    )
    (net (code "101") (name "unconnected-(TO_SENSOR-Pad12)") (class "Default")
      (node (ref "TO_SENSOR") (pin "12") (pinfunction "12_12") (pintype "bidirectional"))
    )
    (net (code "102") (name "unconnected-(TO_SENSOR-Pad13)") (class "Default")
      (node (ref "TO_SENSOR") (pin "13") (pinfunction "13_13") (pintype "bidirectional"))
    )
    (net (code "103") (name "unconnected-(TO_SENSOR-Pad14)") (class "Default")
      (node (ref "TO_SENSOR") (pin "14") (pinfunction "14_14") (pintype "bidirectional"))
    )
    (net (code "104") (name "unconnected-(U2-VOUTD-Pad8)") (class "Default")
      (node (ref "U2") (pin "8") (pinfunction "VOUTD_8") (pintype "input"))
    )
    (net (code "105") (name "unconnected-(U6-SIO2-Pad3)") (class "Default")
      (node (ref "U6") (pin "3") (pinfunction "SIO2_3") (pintype "bidirectional"))
    )
    (net (code "106") (name "unconnected-(U8-RB10-Pad23)") (class "Default")
      (node (ref "U8") (pin "23") (pinfunction "RB10_23") (pintype "bidirectional"))
    )
    (net (code "107") (name "unconnected-(U8-RB11-Pad24)") (class "Default")
      (node (ref "U8") (pin "24") (pinfunction "RB11_24") (pintype "bidirectional"))
    )
    (net (code "108") (name "unconnected-(U8-RB14-Pad29)") (class "Default")
      (node (ref "U8") (pin "29") (pinfunction "RB14_29") (pintype "bidirectional"))
    )
    (net (code "109") (name "unconnected-(U8-RB15-Pad30)") (class "Default")
      (node (ref "U8") (pin "30") (pinfunction "RB15_30") (pintype "bidirectional"))
    )
    (net (code "110") (name "unconnected-(U8-RD6-Pad54)") (class "Default")
      (node (ref "U8") (pin "54") (pinfunction "RD6_54") (pintype "bidirectional"))
    )
    (net (code "111") (name "unconnected-(U8-RF3-Pad33)") (class "Default")
      (node (ref "U8") (pin "33") (pinfunction "RF3_33") (pintype "bidirectional"))
    )
    (net (code "112") (name "unconnected-(U8-RG9-Pad8)") (class "Default")
      (node (ref "U8") (pin "8") (pinfunction "RG9_8") (pintype "bidirectional"))
    )
    (net (code "113") (name "unconnected-(USB-Pad4)") (class "Default")
      (node (ref "USB") (pin "4") (pinfunction "4_4") (pintype "input"))
    )
  )
)
